# Leuchtali_Schematic.net
KiCad netlist of a schematic drawn in EAGLE
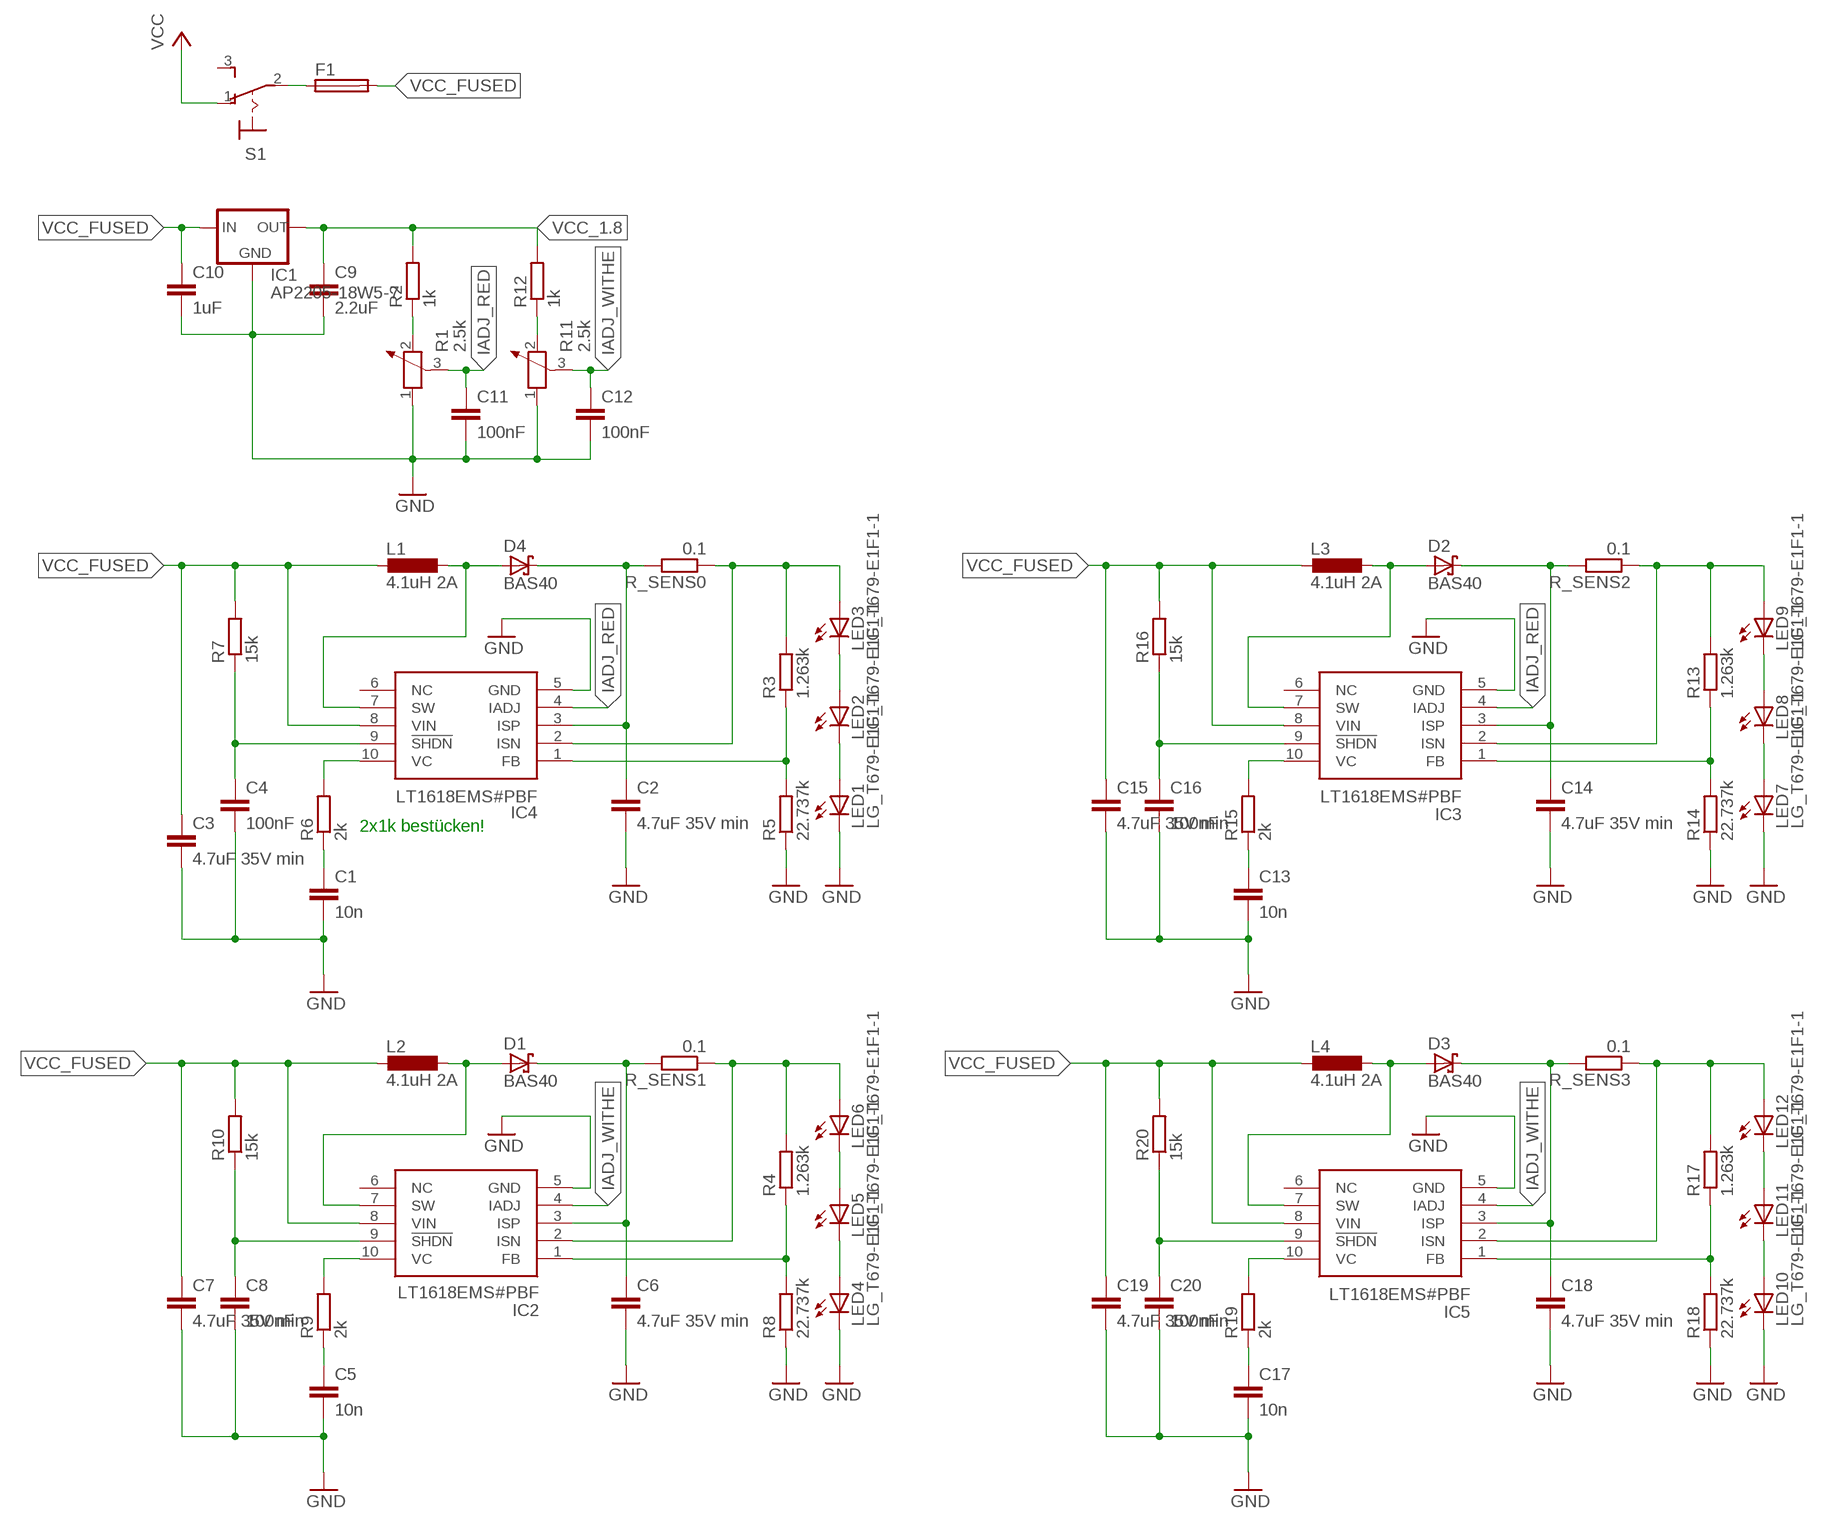
[diagram p0: schematic, sheet 1]

(export (version "E")
  (design (tool "Eeschema 10.0.6"))
  (components
    (comp (ref "C1")
      (value "10n")
      (footprint "eagle-import:C0805")
      (libsource (lib "eagle-import") (part "C-EUC0805"))
    )
    (comp (ref "C2")
      (value "4.7uF 35V min")
      (footprint "eagle-import:C0805")
      (libsource (lib "eagle-import") (part "C-EUC0805"))
    )
    (comp (ref "C3")
      (value "4.7uF 35V min")
      (footprint "eagle-import:C0805")
      (libsource (lib "eagle-import") (part "C-EUC0805"))
    )
    (comp (ref "C4")
      (value "100nF")
      (footprint "eagle-import:C0805")
      (libsource (lib "eagle-import") (part "C-EUC0805"))
    )
    (comp (ref "C5")
      (value "10n")
      (footprint "eagle-import:C0805")
      (libsource (lib "eagle-import") (part "C-EUC0805"))
    )
    (comp (ref "C6")
      (value "4.7uF 35V min")
      (footprint "eagle-import:C0805")
      (libsource (lib "eagle-import") (part "C-EUC0805"))
    )
    (comp (ref "C7")
      (value "4.7uF 35V min")
      (footprint "eagle-import:C0805")
      (libsource (lib "eagle-import") (part "C-EUC0805"))
    )
    (comp (ref "C8")
      (value "100nF")
      (footprint "eagle-import:C0805")
      (libsource (lib "eagle-import") (part "C-EUC0805"))
    )
    (comp (ref "C9")
      (value "2.2uF")
      (footprint "eagle-import:C025-024X044")
      (libsource (lib "eagle-import") (part "C-EU025-024X044"))
    )
    (comp (ref "C10")
      (value "1uF")
      (footprint "eagle-import:C025-024X044")
      (libsource (lib "eagle-import") (part "C-EU025-024X044"))
    )
    (comp (ref "C11")
      (value "100nF")
      (footprint "eagle-import:C025-024X044")
      (libsource (lib "eagle-import") (part "C-EU025-024X044"))
    )
    (comp (ref "C12")
      (value "100nF")
      (footprint "eagle-import:C025-024X044")
      (libsource (lib "eagle-import") (part "C-EU025-024X044"))
    )
    (comp (ref "C13")
      (value "10n")
      (footprint "eagle-import:C0805")
      (libsource (lib "eagle-import") (part "C-EUC0805"))
    )
    (comp (ref "C14")
      (value "4.7uF 35V min")
      (footprint "eagle-import:C0805")
      (libsource (lib "eagle-import") (part "C-EUC0805"))
    )
    (comp (ref "C15")
      (value "4.7uF 35V min")
      (footprint "eagle-import:C0805")
      (libsource (lib "eagle-import") (part "C-EUC0805"))
    )
    (comp (ref "C16")
      (value "100nF")
      (footprint "eagle-import:C0805")
      (libsource (lib "eagle-import") (part "C-EUC0805"))
    )
    (comp (ref "C17")
      (value "10n")
      (footprint "eagle-import:C0805")
      (libsource (lib "eagle-import") (part "C-EUC0805"))
    )
    (comp (ref "C18")
      (value "4.7uF 35V min")
      (footprint "eagle-import:C0805")
      (libsource (lib "eagle-import") (part "C-EUC0805"))
    )
    (comp (ref "C19")
      (value "4.7uF 35V min")
      (footprint "eagle-import:C0805")
      (libsource (lib "eagle-import") (part "C-EUC0805"))
    )
    (comp (ref "C20")
      (value "100nF")
      (footprint "eagle-import:C0805")
      (libsource (lib "eagle-import") (part "C-EUC0805"))
    )
    (comp (ref "D1")
      (value "BAS40")
      (footprint "eagle-import:SOT23")
      (libsource (lib "eagle-import") (part "BAS40"))
    )
    (comp (ref "D2")
      (value "BAS40")
      (footprint "eagle-import:SOT23")
      (libsource (lib "eagle-import") (part "BAS40"))
    )
    (comp (ref "D3")
      (value "BAS40")
      (footprint "eagle-import:SOT23")
      (libsource (lib "eagle-import") (part "BAS40"))
    )
    (comp (ref "D4")
      (value "BAS40")
      (footprint "eagle-import:SOT23")
      (libsource (lib "eagle-import") (part "BAS40"))
    )
    (comp (ref "F1")
      (value "GSH15")
      (footprint "eagle-import:GSH15")
      (fields (field (name "MPN") "64900001039"))
      (libsource (lib "eagle-import") (part "GSH15"))
    )
    (comp (ref "IC1")
      (value "AP2205-18W5-7")
      (footprint "eagle-import:78LXX")
      (libsource (lib "eagle-import") (part "78LXX"))
    )
    (comp (ref "IC2")
      (value "LT1618EMS#PBF")
      (footprint "eagle-import:SOP50P490X110-10N")
      (fields (field (name "MOUSER_PART_NUMBER") "584-LT1618EMS#PBF"))
      (libsource (lib "eagle-import") (part "LT1618EMS#PBF"))
    )
    (comp (ref "IC3")
      (value "LT1618EMS#PBF")
      (footprint "eagle-import:SOP50P490X110-10N")
      (fields (field (name "MOUSER_PART_NUMBER") "584-LT1618EMS#PBF"))
      (libsource (lib "eagle-import") (part "LT1618EMS#PBF"))
    )
    (comp (ref "IC4")
      (value "LT1618EMS#PBF")
      (footprint "eagle-import:SOP50P490X110-10N")
      (fields (field (name "MOUSER_PART_NUMBER") "584-LT1618EMS#PBF"))
      (libsource (lib "eagle-import") (part "LT1618EMS#PBF"))
    )
    (comp (ref "IC5")
      (value "LT1618EMS#PBF")
      (footprint "eagle-import:SOP50P490X110-10N")
      (fields (field (name "MOUSER_PART_NUMBER") "584-LT1618EMS#PBF"))
      (libsource (lib "eagle-import") (part "LT1618EMS#PBF"))
    )
    (comp (ref "L1")
      (value "4.1uH 2A")
      (footprint "eagle-import:0204_5")
      (libsource (lib "eagle-import") (part "L-EU0204/5"))
    )
    (comp (ref "L2")
      (value "4.1uH 2A")
      (footprint "eagle-import:0204_5")
      (libsource (lib "eagle-import") (part "L-EU0204/5"))
    )
    (comp (ref "L3")
      (value "4.1uH 2A")
      (footprint "eagle-import:0204_5")
      (libsource (lib "eagle-import") (part "L-EU0204/5"))
    )
    (comp (ref "L4")
      (value "4.1uH 2A")
      (footprint "eagle-import:0204_5")
      (libsource (lib "eagle-import") (part "L-EU0204/5"))
    )
    (comp (ref "LED1")
      (value "LG_T679-E1F1-1")
      (footprint "eagle-import:PLCC2")
      (libsource (lib "eagle-import") (part "_T679-?-1E1F1LG"))
    )
    (comp (ref "LED2")
      (value "LG_T679-E1F1-1")
      (footprint "eagle-import:PLCC2")
      (libsource (lib "eagle-import") (part "_T679-?-1E1F1LG"))
    )
    (comp (ref "LED3")
      (value "LG_T679-E1F1-1")
      (footprint "eagle-import:PLCC2")
      (libsource (lib "eagle-import") (part "_T679-?-1E1F1LG"))
    )
    (comp (ref "LED4")
      (value "LG_T679-E1F1-1")
      (footprint "eagle-import:PLCC2")
      (libsource (lib "eagle-import") (part "_T679-?-1E1F1LG"))
    )
    (comp (ref "LED5")
      (value "LG_T679-E1F1-1")
      (footprint "eagle-import:PLCC2")
      (libsource (lib "eagle-import") (part "_T679-?-1E1F1LG"))
    )
    (comp (ref "LED6")
      (value "LG_T679-E1F1-1")
      (footprint "eagle-import:PLCC2")
      (libsource (lib "eagle-import") (part "_T679-?-1E1F1LG"))
    )
    (comp (ref "LED7")
      (value "LG_T679-E1F1-1")
      (footprint "eagle-import:PLCC2")
      (libsource (lib "eagle-import") (part "_T679-?-1E1F1LG"))
    )
    (comp (ref "LED8")
      (value "LG_T679-E1F1-1")
      (footprint "eagle-import:PLCC2")
      (libsource (lib "eagle-import") (part "_T679-?-1E1F1LG"))
    )
    (comp (ref "LED9")
      (value "LG_T679-E1F1-1")
      (footprint "eagle-import:PLCC2")
      (libsource (lib "eagle-import") (part "_T679-?-1E1F1LG"))
    )
    (comp (ref "LED10")
      (value "LG_T679-E1F1-1")
      (footprint "eagle-import:PLCC2")
      (libsource (lib "eagle-import") (part "_T679-?-1E1F1LG"))
    )
    (comp (ref "LED11")
      (value "LG_T679-E1F1-1")
      (footprint "eagle-import:PLCC2")
      (libsource (lib "eagle-import") (part "_T679-?-1E1F1LG"))
    )
    (comp (ref "LED12")
      (value "LG_T679-E1F1-1")
      (footprint "eagle-import:PLCC2")
      (libsource (lib "eagle-import") (part "_T679-?-1E1F1LG"))
    )
    (comp (ref "R1")
      (value "2.5k")
      (footprint "eagle-import:PT-10")
      (libsource (lib "eagle-import") (part "POTENTIOMETER_PT-10"))
    )
    (comp (ref "R2")
      (value "1k")
      (footprint "eagle-import:R0805")
      (libsource (lib "eagle-import") (part "R-EU_R0805"))
    )
    (comp (ref "R3")
      (value "1.263k")
      (footprint "eagle-import:R0805")
      (libsource (lib "eagle-import") (part "R-EU_R0805"))
    )
    (comp (ref "R4")
      (value "1.263k")
      (footprint "eagle-import:R0805")
      (libsource (lib "eagle-import") (part "R-EU_R0805"))
    )
    (comp (ref "R5")
      (value "22.737k")
      (footprint "eagle-import:R0805")
      (libsource (lib "eagle-import") (part "R-EU_R0805"))
    )
    (comp (ref "R6")
      (value "2k")
      (footprint "eagle-import:R0805")
      (libsource (lib "eagle-import") (part "R-EU_R0805"))
    )
    (comp (ref "R7")
      (value "15k")
      (footprint "eagle-import:R0805")
      (libsource (lib "eagle-import") (part "R-EU_R0805"))
    )
    (comp (ref "R8")
      (value "22.737k")
      (footprint "eagle-import:R0805")
      (libsource (lib "eagle-import") (part "R-EU_R0805"))
    )
    (comp (ref "R9")
      (value "2k")
      (footprint "eagle-import:R0805")
      (libsource (lib "eagle-import") (part "R-EU_R0805"))
    )
    (comp (ref "R10")
      (value "15k")
      (footprint "eagle-import:R0805")
      (libsource (lib "eagle-import") (part "R-EU_R0805"))
    )
    (comp (ref "R11")
      (value "2.5k")
      (footprint "eagle-import:PT-10")
      (libsource (lib "eagle-import") (part "POTENTIOMETER_PT-10"))
    )
    (comp (ref "R12")
      (value "1k")
      (footprint "eagle-import:R0805")
      (libsource (lib "eagle-import") (part "R-EU_R0805"))
    )
    (comp (ref "R13")
      (value "1.263k")
      (footprint "eagle-import:R0805")
      (libsource (lib "eagle-import") (part "R-EU_R0805"))
    )
    (comp (ref "R14")
      (value "22.737k")
      (footprint "eagle-import:R0805")
      (libsource (lib "eagle-import") (part "R-EU_R0805"))
    )
    (comp (ref "R15")
      (value "2k")
      (footprint "eagle-import:R0805")
      (libsource (lib "eagle-import") (part "R-EU_R0805"))
    )
    (comp (ref "R16")
      (value "15k")
      (footprint "eagle-import:R0805")
      (libsource (lib "eagle-import") (part "R-EU_R0805"))
    )
    (comp (ref "R17")
      (value "1.263k")
      (footprint "eagle-import:R0805")
      (libsource (lib "eagle-import") (part "R-EU_R0805"))
    )
    (comp (ref "R18")
      (value "22.737k")
      (footprint "eagle-import:R0805")
      (libsource (lib "eagle-import") (part "R-EU_R0805"))
    )
    (comp (ref "R19")
      (value "2k")
      (footprint "eagle-import:R0805")
      (libsource (lib "eagle-import") (part "R-EU_R0805"))
    )
    (comp (ref "R20")
      (value "15k")
      (footprint "eagle-import:R0805")
      (libsource (lib "eagle-import") (part "R-EU_R0805"))
    )
    (comp (ref "R_SENS0")
      (value "0.1")
      (footprint "eagle-import:R0805")
      (libsource (lib "eagle-import") (part "R-EU_R0805"))
    )
    (comp (ref "R_SENS1")
      (value "0.1")
      (footprint "eagle-import:R0805")
      (libsource (lib "eagle-import") (part "R-EU_R0805"))
    )
    (comp (ref "R_SENS2")
      (value "0.1")
      (footprint "eagle-import:R0805")
      (libsource (lib "eagle-import") (part "R-EU_R0805"))
    )
    (comp (ref "R_SENS3")
      (value "0.1")
      (footprint "eagle-import:R0805")
      (libsource (lib "eagle-import") (part "R-EU_R0805"))
    )
    (comp (ref "S1")
      (value "320-916")
      (footprint "eagle-import:320-916")
      (libsource (lib "eagle-import") (part "320-916"))
    )
  )
  (nets
    (net (code "1") (name "GND") (class "Default")
      (node (ref "C1") (pin "2") (pinfunction "2_2") (pintype "passive"))
      (node (ref "C10") (pin "2") (pinfunction "2_2") (pintype "passive"))
      (node (ref "C11") (pin "2") (pinfunction "2_2") (pintype "passive"))
      (node (ref "C12") (pin "2") (pinfunction "2_2") (pintype "passive"))
      (node (ref "C13") (pin "2") (pinfunction "2_2") (pintype "passive"))
      (node (ref "C14") (pin "2") (pinfunction "2_2") (pintype "passive"))
      (node (ref "C15") (pin "2") (pinfunction "2_2") (pintype "passive"))
      (node (ref "C16") (pin "2") (pinfunction "2_2") (pintype "passive"))
      (node (ref "C17") (pin "2") (pinfunction "2_2") (pintype "passive"))
      (node (ref "C18") (pin "2") (pinfunction "2_2") (pintype "passive"))
      (node (ref "C19") (pin "2") (pinfunction "2_2") (pintype "passive"))
      (node (ref "C2") (pin "2") (pinfunction "2_2") (pintype "passive"))
      (node (ref "C20") (pin "2") (pinfunction "2_2") (pintype "passive"))
      (node (ref "C3") (pin "2") (pinfunction "2_2") (pintype "passive"))
      (node (ref "C4") (pin "2") (pinfunction "2_2") (pintype "passive"))
      (node (ref "C5") (pin "2") (pinfunction "2_2") (pintype "passive"))
      (node (ref "C6") (pin "2") (pinfunction "2_2") (pintype "passive"))
      (node (ref "C7") (pin "2") (pinfunction "2_2") (pintype "passive"))
      (node (ref "C8") (pin "2") (pinfunction "2_2") (pintype "passive"))
      (node (ref "C9") (pin "2") (pinfunction "2_2") (pintype "passive"))
      (node (ref "IC1") (pin "GND") (pinfunction "GND_GND") (pintype "input"))
      (node (ref "IC2") (pin "5") (pinfunction "GND_5") (pintype "bidirectional"))
      (node (ref "IC3") (pin "5") (pinfunction "GND_5") (pintype "bidirectional"))
      (node (ref "IC4") (pin "5") (pinfunction "GND_5") (pintype "bidirectional"))
      (node (ref "IC5") (pin "5") (pinfunction "GND_5") (pintype "bidirectional"))
      (node (ref "LED1") (pin "C") (pinfunction "C_C") (pintype "passive"))
      (node (ref "LED10") (pin "C") (pinfunction "C_C") (pintype "passive"))
      (node (ref "LED4") (pin "C") (pinfunction "C_C") (pintype "passive"))
      (node (ref "LED7") (pin "C") (pinfunction "C_C") (pintype "passive"))
      (node (ref "R1") (pin "1") (pinfunction "1_1") (pintype "passive"))
      (node (ref "R11") (pin "1") (pinfunction "1_1") (pintype "passive"))
      (node (ref "R14") (pin "1") (pinfunction "1_1") (pintype "passive"))
      (node (ref "R18") (pin "1") (pinfunction "1_1") (pintype "passive"))
      (node (ref "R5") (pin "1") (pinfunction "1_1") (pintype "passive"))
      (node (ref "R8") (pin "1") (pinfunction "1_1") (pintype "passive"))
    )
    (net (code "2") (name "IADJ_RED") (class "Default")
      (node (ref "C11") (pin "1") (pinfunction "1_1") (pintype "passive"))
      (node (ref "IC3") (pin "4") (pinfunction "IADJ_4") (pintype "bidirectional"))
      (node (ref "IC4") (pin "4") (pinfunction "IADJ_4") (pintype "bidirectional"))
      (node (ref "R1") (pin "3") (pinfunction "3_3") (pintype "passive"))
    )
    (net (code "3") (name "IADJ_WITHE") (class "Default")
      (node (ref "C12") (pin "1") (pinfunction "1_1") (pintype "passive"))
      (node (ref "IC2") (pin "4") (pinfunction "IADJ_4") (pintype "bidirectional"))
      (node (ref "IC5") (pin "4") (pinfunction "IADJ_4") (pintype "bidirectional"))
      (node (ref "R11") (pin "3") (pinfunction "3_3") (pintype "passive"))
    )
    (net (code "4") (name "Net-(C1-Pad1)") (class "Default")
      (node (ref "C1") (pin "1") (pinfunction "1_1") (pintype "passive"))
      (node (ref "R6") (pin "1") (pinfunction "1_1") (pintype "passive"))
    )
    (net (code "5") (name "Net-(C5-Pad1)") (class "Default")
      (node (ref "C5") (pin "1") (pinfunction "1_1") (pintype "passive"))
      (node (ref "R9") (pin "1") (pinfunction "1_1") (pintype "passive"))
    )
    (net (code "6") (name "Net-(C13-Pad1)") (class "Default")
      (node (ref "C13") (pin "1") (pinfunction "1_1") (pintype "passive"))
      (node (ref "R15") (pin "1") (pinfunction "1_1") (pintype "passive"))
    )
    (net (code "7") (name "Net-(C17-Pad1)") (class "Default")
      (node (ref "C17") (pin "1") (pinfunction "1_1") (pintype "passive"))
      (node (ref "R19") (pin "1") (pinfunction "1_1") (pintype "passive"))
    )
    (net (code "8") (name "Net-(D1-A)") (class "Default")
      (node (ref "D1") (pin "1") (pinfunction "A_1") (pintype "passive"))
      (node (ref "IC2") (pin "7") (pinfunction "SW_7") (pintype "bidirectional"))
      (node (ref "L2") (pin "1") (pinfunction "1_1") (pintype "passive"))
    )
    (net (code "9") (name "Net-(D1-C)") (class "Default")
      (node (ref "C6") (pin "1") (pinfunction "1_1") (pintype "passive"))
      (node (ref "D1") (pin "3") (pinfunction "C_3") (pintype "passive"))
      (node (ref "IC2") (pin "3") (pinfunction "ISP_3") (pintype "bidirectional"))
      (node (ref "R_SENS1") (pin "2") (pinfunction "2_2") (pintype "passive"))
    )
    (net (code "10") (name "Net-(D2-A)") (class "Default")
      (node (ref "D2") (pin "1") (pinfunction "A_1") (pintype "passive"))
      (node (ref "IC3") (pin "7") (pinfunction "SW_7") (pintype "bidirectional"))
      (node (ref "L3") (pin "1") (pinfunction "1_1") (pintype "passive"))
    )
    (net (code "11") (name "Net-(D2-C)") (class "Default")
      (node (ref "C14") (pin "1") (pinfunction "1_1") (pintype "passive"))
      (node (ref "D2") (pin "3") (pinfunction "C_3") (pintype "passive"))
      (node (ref "IC3") (pin "3") (pinfunction "ISP_3") (pintype "bidirectional"))
      (node (ref "R_SENS2") (pin "2") (pinfunction "2_2") (pintype "passive"))
    )
    (net (code "12") (name "Net-(D3-A)") (class "Default")
      (node (ref "D3") (pin "1") (pinfunction "A_1") (pintype "passive"))
      (node (ref "IC5") (pin "7") (pinfunction "SW_7") (pintype "bidirectional"))
      (node (ref "L4") (pin "1") (pinfunction "1_1") (pintype "passive"))
    )
    (net (code "13") (name "Net-(D3-C)") (class "Default")
      (node (ref "C18") (pin "1") (pinfunction "1_1") (pintype "passive"))
      (node (ref "D3") (pin "3") (pinfunction "C_3") (pintype "passive"))
      (node (ref "IC5") (pin "3") (pinfunction "ISP_3") (pintype "bidirectional"))
      (node (ref "R_SENS3") (pin "2") (pinfunction "2_2") (pintype "passive"))
    )
    (net (code "14") (name "Net-(D4-A)") (class "Default")
      (node (ref "D4") (pin "1") (pinfunction "A_1") (pintype "passive"))
      (node (ref "IC4") (pin "7") (pinfunction "SW_7") (pintype "bidirectional"))
      (node (ref "L1") (pin "1") (pinfunction "1_1") (pintype "passive"))
    )
    (net (code "15") (name "Net-(D4-C)") (class "Default")
      (node (ref "C2") (pin "1") (pinfunction "1_1") (pintype "passive"))
      (node (ref "D4") (pin "3") (pinfunction "C_3") (pintype "passive"))
      (node (ref "IC4") (pin "3") (pinfunction "ISP_3") (pintype "bidirectional"))
      (node (ref "R_SENS0") (pin "2") (pinfunction "2_2") (pintype "passive"))
    )
    (net (code "16") (name "Net-(IC2-FB)") (class "Default")
      (node (ref "IC2") (pin "1") (pinfunction "FB_1") (pintype "bidirectional"))
      (node (ref "R4") (pin "1") (pinfunction "1_1") (pintype "passive"))
      (node (ref "R8") (pin "2") (pinfunction "2_2") (pintype "passive"))
    )
    (net (code "17") (name "Net-(IC2-ISN)") (class "Default")
      (node (ref "IC2") (pin "2") (pinfunction "ISN_2") (pintype "bidirectional"))
      (node (ref "LED6") (pin "A") (pinfunction "A_A") (pintype "passive"))
      (node (ref "R4") (pin "2") (pinfunction "2_2") (pintype "passive"))
      (node (ref "R_SENS1") (pin "1") (pinfunction "1_1") (pintype "passive"))
    )
    (net (code "18") (name "Net-(IC2-VC)") (class "Default")
      (node (ref "IC2") (pin "10") (pinfunction "VC_10") (pintype "bidirectional"))
      (node (ref "R9") (pin "2") (pinfunction "2_2") (pintype "passive"))
    )
    (net (code "19") (name "Net-(IC2-~{SHDN})") (class "Default")
      (node (ref "C8") (pin "1") (pinfunction "1_1") (pintype "passive"))
      (node (ref "IC2") (pin "9") (pinfunction "~{SHDN}_9") (pintype "bidirectional"))
      (node (ref "R10") (pin "1") (pinfunction "1_1") (pintype "passive"))
    )
    (net (code "20") (name "Net-(IC3-FB)") (class "Default")
      (node (ref "IC3") (pin "1") (pinfunction "FB_1") (pintype "bidirectional"))
      (node (ref "R13") (pin "1") (pinfunction "1_1") (pintype "passive"))
      (node (ref "R14") (pin "2") (pinfunction "2_2") (pintype "passive"))
    )
    (net (code "21") (name "Net-(IC3-ISN)") (class "Default")
      (node (ref "IC3") (pin "2") (pinfunction "ISN_2") (pintype "bidirectional"))
      (node (ref "LED9") (pin "A") (pinfunction "A_A") (pintype "passive"))
      (node (ref "R13") (pin "2") (pinfunction "2_2") (pintype "passive"))
      (node (ref "R_SENS2") (pin "1") (pinfunction "1_1") (pintype "passive"))
    )
    (net (code "22") (name "Net-(IC3-VC)") (class "Default")
      (node (ref "IC3") (pin "10") (pinfunction "VC_10") (pintype "bidirectional"))
      (node (ref "R15") (pin "2") (pinfunction "2_2") (pintype "passive"))
    )
    (net (code "23") (name "Net-(IC3-~{SHDN})") (class "Default")
      (node (ref "C16") (pin "1") (pinfunction "1_1") (pintype "passive"))
      (node (ref "IC3") (pin "9") (pinfunction "~{SHDN}_9") (pintype "bidirectional"))
      (node (ref "R16") (pin "1") (pinfunction "1_1") (pintype "passive"))
    )
    (net (code "24") (name "Net-(IC4-FB)") (class "Default")
      (node (ref "IC4") (pin "1") (pinfunction "FB_1") (pintype "bidirectional"))
      (node (ref "R3") (pin "1") (pinfunction "1_1") (pintype "passive"))
      (node (ref "R5") (pin "2") (pinfunction "2_2") (pintype "passive"))
    )
    (net (code "25") (name "Net-(IC4-ISN)") (class "Default")
      (node (ref "IC4") (pin "2") (pinfunction "ISN_2") (pintype "bidirectional"))
      (node (ref "LED3") (pin "A") (pinfunction "A_A") (pintype "passive"))
      (node (ref "R3") (pin "2") (pinfunction "2_2") (pintype "passive"))
      (node (ref "R_SENS0") (pin "1") (pinfunction "1_1") (pintype "passive"))
    )
    (net (code "26") (name "Net-(IC4-VC)") (class "Default")
      (node (ref "IC4") (pin "10") (pinfunction "VC_10") (pintype "bidirectional"))
      (node (ref "R6") (pin "2") (pinfunction "2_2") (pintype "passive"))
    )
    (net (code "27") (name "Net-(IC4-~{SHDN})") (class "Default")
      (node (ref "C4") (pin "1") (pinfunction "1_1") (pintype "passive"))
      (node (ref "IC4") (pin "9") (pinfunction "~{SHDN}_9") (pintype "bidirectional"))
      (node (ref "R7") (pin "1") (pinfunction "1_1") (pintype "passive"))
    )
    (net (code "28") (name "Net-(IC5-FB)") (class "Default")
      (node (ref "IC5") (pin "1") (pinfunction "FB_1") (pintype "bidirectional"))
      (node (ref "R17") (pin "1") (pinfunction "1_1") (pintype "passive"))
      (node (ref "R18") (pin "2") (pinfunction "2_2") (pintype "passive"))
    )
    (net (code "29") (name "Net-(IC5-ISN)") (class "Default")
      (node (ref "IC5") (pin "2") (pinfunction "ISN_2") (pintype "bidirectional"))
      (node (ref "LED12") (pin "A") (pinfunction "A_A") (pintype "passive"))
      (node (ref "R17") (pin "2") (pinfunction "2_2") (pintype "passive"))
      (node (ref "R_SENS3") (pin "1") (pinfunction "1_1") (pintype "passive"))
    )
    (net (code "30") (name "Net-(IC5-VC)") (class "Default")
      (node (ref "IC5") (pin "10") (pinfunction "VC_10") (pintype "bidirectional"))
      (node (ref "R19") (pin "2") (pinfunction "2_2") (pintype "passive"))
    )
    (net (code "31") (name "Net-(IC5-~{SHDN})") (class "Default")
      (node (ref "C20") (pin "1") (pinfunction "1_1") (pintype "passive"))
      (node (ref "IC5") (pin "9") (pinfunction "~{SHDN}_9") (pintype "bidirectional"))
      (node (ref "R20") (pin "1") (pinfunction "1_1") (pintype "passive"))
    )
    (net (code "32") (name "Net-(LED1-PadA)") (class "Default")
      (node (ref "LED1") (pin "A") (pinfunction "A_A") (pintype "passive"))
      (node (ref "LED2") (pin "C") (pinfunction "C_C") (pintype "passive"))
    )
    (net (code "33") (name "Net-(LED2-PadA)") (class "Default")
      (node (ref "LED2") (pin "A") (pinfunction "A_A") (pintype "passive"))
      (node (ref "LED3") (pin "C") (pinfunction "C_C") (pintype "passive"))
    )
    (net (code "34") (name "Net-(LED4-PadA)") (class "Default")
      (node (ref "LED4") (pin "A") (pinfunction "A_A") (pintype "passive"))
      (node (ref "LED5") (pin "C") (pinfunction "C_C") (pintype "passive"))
    )
    (net (code "35") (name "Net-(LED5-PadA)") (class "Default")
      (node (ref "LED5") (pin "A") (pinfunction "A_A") (pintype "passive"))
      (node (ref "LED6") (pin "C") (pinfunction "C_C") (pintype "passive"))
    )
    (net (code "36") (name "Net-(LED7-PadA)") (class "Default")
      (node (ref "LED7") (pin "A") (pinfunction "A_A") (pintype "passive"))
      (node (ref "LED8") (pin "C") (pinfunction "C_C") (pintype "passive"))
    )
    (net (code "37") (name "Net-(LED8-PadA)") (class "Default")
      (node (ref "LED8") (pin "A") (pinfunction "A_A") (pintype "passive"))
      (node (ref "LED9") (pin "C") (pinfunction "C_C") (pintype "passive"))
    )
    (net (code "38") (name "Net-(LED10-PadA)") (class "Default")
      (node (ref "LED10") (pin "A") (pinfunction "A_A") (pintype "passive"))
      (node (ref "LED11") (pin "C") (pinfunction "C_C") (pintype "passive"))
    )
    (net (code "39") (name "Net-(LED11-PadA)") (class "Default")
      (node (ref "LED11") (pin "A") (pinfunction "A_A") (pintype "passive"))
      (node (ref "LED12") (pin "C") (pinfunction "C_C") (pintype "passive"))
    )
    (net (code "40") (name "Net-(R1-Pad2)") (class "Default")
      (node (ref "R1") (pin "2") (pinfunction "2_2") (pintype "passive"))
      (node (ref "R2") (pin "1") (pinfunction "1_1") (pintype "passive"))
    )
    (net (code "41") (name "Net-(R11-Pad2)") (class "Default")
      (node (ref "R11") (pin "2") (pinfunction "2_2") (pintype "passive"))
      (node (ref "R12") (pin "1") (pinfunction "1_1") (pintype "passive"))
    )
    (net (code "42") (name "Net-(S1-P)") (class "Default")
      (node (ref "F1") (pin "1") (pinfunction "1_1") (pintype "passive"))
      (node (ref "S1") (pin "2") (pinfunction "P_2") (pintype "passive"))
    )
    (net (code "43") (name "VCC") (class "Default")
      (node (ref "S1") (pin "1") (pinfunction "O_1") (pintype "passive"))
    )
    (net (code "44") (name "VCC_1.8") (class "Default")
      (node (ref "C9") (pin "1") (pinfunction "1_1") (pintype "passive"))
      (node (ref "IC1") (pin "OUT") (pinfunction "OUT_OUT") (pintype "passive"))
      (node (ref "R12") (pin "2") (pinfunction "2_2") (pintype "passive"))
      (node (ref "R2") (pin "2") (pinfunction "2_2") (pintype "passive"))
    )
    (net (code "45") (name "VCC_FUSED") (class "Default")
      (node (ref "C10") (pin "1") (pinfunction "1_1") (pintype "passive"))
      (node (ref "C15") (pin "1") (pinfunction "1_1") (pintype "passive"))
      (node (ref "C19") (pin "1") (pinfunction "1_1") (pintype "passive"))
      (node (ref "C3") (pin "1") (pinfunction "1_1") (pintype "passive"))
      (node (ref "C7") (pin "1") (pinfunction "1_1") (pintype "passive"))
      (node (ref "F1") (pin "2") (pinfunction "2_2") (pintype "passive"))
      (node (ref "IC1") (pin "IN") (pinfunction "IN_IN") (pintype "input"))
      (node (ref "IC2") (pin "8") (pinfunction "VIN_8") (pintype "bidirectional"))
      (node (ref "IC3") (pin "8") (pinfunction "VIN_8") (pintype "bidirectional"))
      (node (ref "IC4") (pin "8") (pinfunction "VIN_8") (pintype "bidirectional"))
      (node (ref "IC5") (pin "8") (pinfunction "VIN_8") (pintype "bidirectional"))
      (node (ref "L1") (pin "2") (pinfunction "2_2") (pintype "passive"))
      (node (ref "L2") (pin "2") (pinfunction "2_2") (pintype "passive"))
      (node (ref "L3") (pin "2") (pinfunction "2_2") (pintype "passive"))
      (node (ref "L4") (pin "2") (pinfunction "2_2") (pintype "passive"))
      (node (ref "R10") (pin "2") (pinfunction "2_2") (pintype "passive"))
      (node (ref "R16") (pin "2") (pinfunction "2_2") (pintype "passive"))
      (node (ref "R20") (pin "2") (pinfunction "2_2") (pintype "passive"))
      (node (ref "R7") (pin "2") (pinfunction "2_2") (pintype "passive"))
    )
    (net (code "46") (name "unconnected-(IC2-NC-Pad6)") (class "Default")
      (node (ref "IC2") (pin "6") (pinfunction "NC_6") (pintype "no_connect"))
    )
    (net (code "47") (name "unconnected-(IC3-NC-Pad6)") (class "Default")
      (node (ref "IC3") (pin "6") (pinfunction "NC_6") (pintype "no_connect"))
    )
    (net (code "48") (name "unconnected-(IC4-NC-Pad6)") (class "Default")
      (node (ref "IC4") (pin "6") (pinfunction "NC_6") (pintype "no_connect"))
    )
    (net (code "49") (name "unconnected-(IC5-NC-Pad6)") (class "Default")
      (node (ref "IC5") (pin "6") (pinfunction "NC_6") (pintype "no_connect"))
    )
    (net (code "50") (name "unconnected-(S1-S-Pad3)") (class "Default")
      (node (ref "S1") (pin "3") (pinfunction "S_3") (pintype "passive"))
    )
  )
)
